# DRIVER_WITH_MOS.net
KiCad netlist of a schematic drawn in Altium Designer
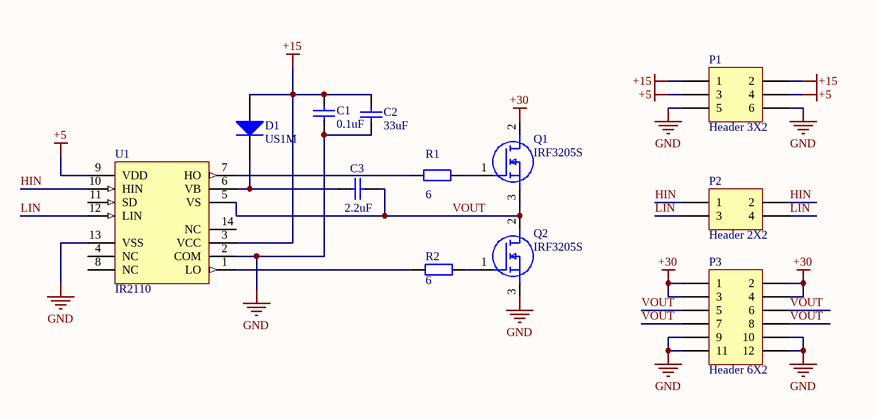
[diagram p0: DRIVER_WITH_MOS.SchDoc]

(export (version "E")
  (design (tool "Eeschema 10.0.6"))
  (components
    (comp (ref "C1")
      (value "0.1uF")
      (footprint "1608[0603]")
      (description "Capacitor")
      (fields (field (name "Comment") "Cap") (field (name "PUBLISHER") "Altium Limited"))
      (libsource (lib "Miscellaneous Devices") (part "Cap"))
    )
    (comp (ref "C2")
      (value "33uF")
      (footprint "C1210")
      (description "Capacitor")
      (fields (field (name "Comment") "Cap") (field (name "PUBLISHER") "Altium Limited"))
      (libsource (lib "Miscellaneous Devices") (part "Cap"))
    )
    (comp (ref "C3")
      (value "2.2uF")
      (footprint "C1210")
      (description "Capacitor")
      (fields (field (name "Comment") "Cap") (field (name "PUBLISHER") "Altium Limited"))
      (libsource (lib "Miscellaneous Devices") (part "Cap"))
    )
    (comp (ref "D1")
      (value "US1M")
      (footprint "DIOM5127X229N")
      (description "High Conductance Fast Diode")
      (fields (field (name "PUBLISHER") "Altium Limited"))
      (libsource (lib "FSC Discrete Diode") (part "1N4148"))
    )
    (comp (ref "P1")
      (value "Header 3X2")
      (footprint "HDR2X3")
      (description "Header, 3-Pin, Dual row")
      (fields (field (name "PUBLISHER") "Altium Limited"))
      (libsource (lib "Miscellaneous Connectors") (part "Header 3X2"))
    )
    (comp (ref "P2")
      (value "Header 2X2")
      (footprint "HDR2X2")
      (description "Header, 2-Pin, Dual row")
      (fields (field (name "PUBLISHER") "Altium Limited"))
      (libsource (lib "Miscellaneous Connectors") (part "Header 2X2"))
    )
    (comp (ref "P3")
      (value "Header 6X2")
      (footprint "HDR2X6")
      (description "Header, 6-Pin, Dual row")
      (fields (field (name "PUBLISHER") "Altium Limited"))
      (libsource (lib "Miscellaneous Connectors") (part "Header 6X2"))
    )
    (comp (ref "Q1")
      (value "IRF3205S")
      (footprint "SamacSys:TO254P469X1042X1930-3P")
      (description "MOSFET (N-Channel)")
      (fields (field (name "RS PART NUMBER") "3954859"))
      (libsource (lib "*") (part "IRF3205S"))
    )
    (comp (ref "Q2")
      (value "IRF3205S")
      (footprint "SamacSys:TO254P469X1042X1930-3P")
      (description "MOSFET (N-Channel)")
      (fields (field (name "RS PART NUMBER") "3954859"))
      (libsource (lib "*") (part "IRF3205S"))
    )
    (comp (ref "R1")
      (value "6")
      (footprint "0402")
      (description "Resistor")
      (fields (field (name "Comment") "Res2") (field (name "PUBLISHER") "Altium Limited"))
      (libsource (lib "Miscellaneous Devices") (part "Res2"))
    )
    (comp (ref "R2")
      (value "6")
      (footprint "0402")
      (description "Resistor")
      (fields (field (name "Comment") "Res2") (field (name "PUBLISHER") "Altium Limited"))
      (libsource (lib "Miscellaneous Devices") (part "Res2"))
    )
    (comp (ref "U1")
      (value "IR2110")
      (footprint "DIP-14")
      (description "High and Low Side Driver")
      (fields (field (name "PUBLISHER") "Altium Limited"))
      (libsource (lib "IR Interface Bridge Driver") (part "IR2110"))
    )
  )
  (nets
    (net (code "1") (name "+5") (class "Default")
      (node (ref "P1") (pin "3") (pinfunction "3_3") (pintype "passive"))
      (node (ref "P1") (pin "4") (pinfunction "4_4") (pintype "passive"))
      (node (ref "U1") (pin "9") (pinfunction "VDD_9") (pintype "power_in"))
    )
    (net (code "2") (name "+15") (class "Default")
      (node (ref "C1") (pin "2") (pinfunction "2_2") (pintype "passive"))
      (node (ref "C2") (pin "1") (pinfunction "1_1") (pintype "passive"))
      (node (ref "D1") (pin "1") (pinfunction "A_1") (pintype "passive"))
      (node (ref "P1") (pin "1") (pinfunction "1_1") (pintype "passive"))
      (node (ref "P1") (pin "2") (pinfunction "2_2") (pintype "passive"))
      (node (ref "U1") (pin "3") (pinfunction "VCC_3") (pintype "power_in"))
    )
    (net (code "3") (name "+30") (class "Default")
      (node (ref "P3") (pin "1") (pinfunction "1_1") (pintype "passive"))
      (node (ref "P3") (pin "2") (pinfunction "2_2") (pintype "passive"))
      (node (ref "P3") (pin "3") (pinfunction "3_3") (pintype "passive"))
      (node (ref "P3") (pin "4") (pinfunction "4_4") (pintype "passive"))
      (node (ref "Q1") (pin "2") (pinfunction "D_2") (pintype "passive"))
    )
    (net (code "4") (name "/HIN") (class "Default")
      (node (ref "P2") (pin "1") (pinfunction "1_1") (pintype "passive"))
      (node (ref "P2") (pin "2") (pinfunction "2_2") (pintype "passive"))
      (node (ref "U1") (pin "10") (pinfunction "HIN_10") (pintype "input"))
    )
    (net (code "5") (name "/LIN") (class "Default")
      (node (ref "P2") (pin "3") (pinfunction "3_3") (pintype "passive"))
      (node (ref "P2") (pin "4") (pinfunction "4_4") (pintype "passive"))
      (node (ref "U1") (pin "12") (pinfunction "LIN_12") (pintype "input"))
    )
    (net (code "6") (name "/VOUT") (class "Default")
      (node (ref "C3") (pin "2") (pinfunction "2_2") (pintype "passive"))
      (node (ref "P3") (pin "5") (pinfunction "5_5") (pintype "passive"))
      (node (ref "P3") (pin "6") (pinfunction "6_6") (pintype "passive"))
      (node (ref "P3") (pin "7") (pinfunction "7_7") (pintype "passive"))
      (node (ref "P3") (pin "8") (pinfunction "8_8") (pintype "passive"))
      (node (ref "Q1") (pin "3") (pinfunction "S_3") (pintype "passive"))
      (node (ref "Q2") (pin "2") (pinfunction "D_2") (pintype "passive"))
      (node (ref "U1") (pin "5") (pinfunction "VS_5") (pintype "power_in"))
    )
    (net (code "7") (name "GND") (class "Default")
      (node (ref "C1") (pin "1") (pinfunction "1_1") (pintype "passive"))
      (node (ref "C2") (pin "2") (pinfunction "2_2") (pintype "passive"))
      (node (ref "P1") (pin "5") (pinfunction "5_5") (pintype "passive"))
      (node (ref "P1") (pin "6") (pinfunction "6_6") (pintype "passive"))
      (node (ref "P3") (pin "10") (pinfunction "10_10") (pintype "passive"))
      (node (ref "P3") (pin "11") (pinfunction "11_11") (pintype "passive"))
      (node (ref "P3") (pin "12") (pinfunction "12_12") (pintype "passive"))
      (node (ref "P3") (pin "9") (pinfunction "9_9") (pintype "passive"))
      (node (ref "Q2") (pin "3") (pinfunction "S_3") (pintype "passive"))
      (node (ref "U1") (pin "13") (pinfunction "VSS_13") (pintype "power_in"))
      (node (ref "U1") (pin "2") (pinfunction "COM_2") (pintype "power_in"))
    )
    (net (code "8") (name "Net-(D1-K)") (class "Default")
      (node (ref "C3") (pin "1") (pinfunction "1_1") (pintype "passive"))
      (node (ref "D1") (pin "2") (pinfunction "K_2") (pintype "passive"))
      (node (ref "U1") (pin "6") (pinfunction "VB_6") (pintype "power_in"))
    )
    (net (code "9") (name "Net-(Q1-G)") (class "Default")
      (node (ref "Q1") (pin "1") (pinfunction "G_1") (pintype "passive"))
      (node (ref "R1") (pin "2") (pinfunction "2_2") (pintype "passive"))
    )
    (net (code "10") (name "Net-(Q2-G)") (class "Default")
      (node (ref "Q2") (pin "1") (pinfunction "G_1") (pintype "passive"))
      (node (ref "R2") (pin "2") (pinfunction "2_2") (pintype "passive"))
    )
    (net (code "11") (name "Net-(U1-HO)") (class "Default")
      (node (ref "R1") (pin "1") (pinfunction "1_1") (pintype "passive"))
      (node (ref "U1") (pin "7") (pinfunction "HO_7") (pintype "output"))
    )
    (net (code "12") (name "Net-(U1-LO)") (class "Default")
      (node (ref "R2") (pin "1") (pinfunction "1_1") (pintype "passive"))
      (node (ref "U1") (pin "1") (pinfunction "LO_1") (pintype "output"))
    )
    (net (code "13") (name "unconnected-(U1-NC-Pad4)") (class "Default")
      (node (ref "U1") (pin "4") (pinfunction "NC_4") (pintype "passive"))
    )
    (net (code "14") (name "unconnected-(U1-NC-Pad8)") (class "Default")
      (node (ref "U1") (pin "8") (pinfunction "NC_8") (pintype "passive"))
    )
    (net (code "15") (name "unconnected-(U1-NC-Pad14)") (class "Default")
      (node (ref "U1") (pin "14") (pinfunction "NC_14") (pintype "passive"))
    )
    (net (code "16") (name "unconnected-(U1-SD-Pad11)") (class "Default")
      (node (ref "U1") (pin "11") (pinfunction "SD_11") (pintype "input"))
    )
  )
)
